# Mono_Audio_Amp.net
KiCad netlist of a schematic drawn in EAGLE
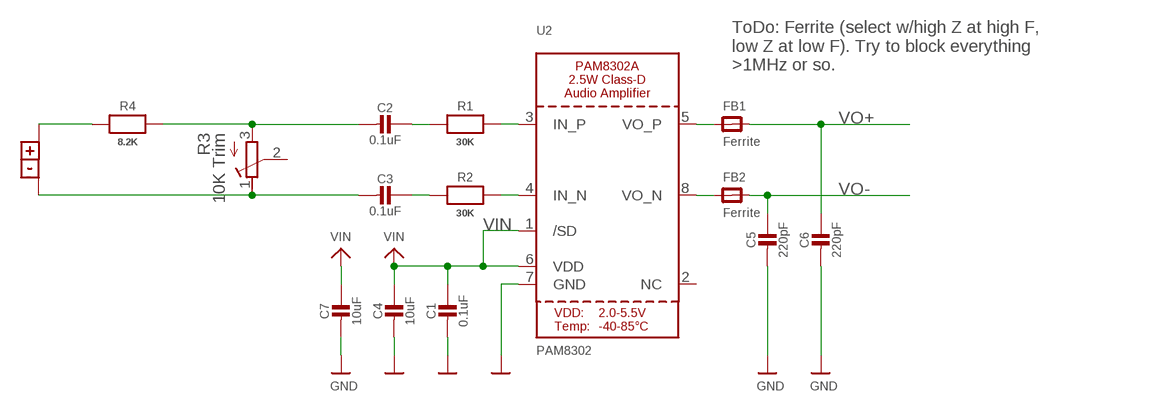
[diagram p0: schematic, sheet 1]

(export (version "E")
  (design (tool "Eeschema 10.0.6"))
  (components
    (comp (ref "C1")
      (value "0.1uF")
      (footprint "eagle-import:0603-NO")
      (libsource (lib "eagle-import") (part "CAP_CERAMIC0603_NO"))
    )
    (comp (ref "C2")
      (value "0.1uF")
      (footprint "eagle-import:0603-NO")
      (libsource (lib "eagle-import") (part "CAP_CERAMIC0603_NO"))
    )
    (comp (ref "C3")
      (value "0.1uF")
      (footprint "eagle-import:0603-NO")
      (libsource (lib "eagle-import") (part "CAP_CERAMIC0603_NO"))
    )
    (comp (ref "C4")
      (value "10uF")
      (footprint "eagle-import:0805-NO")
      (libsource (lib "eagle-import") (part "CAP_CERAMIC0805-NOOUTLINE"))
    )
    (comp (ref "C5")
      (value "220pF")
      (footprint "eagle-import:0603-NO")
      (libsource (lib "eagle-import") (part "CAP_CERAMIC0603_NO"))
    )
    (comp (ref "C6")
      (value "220pF")
      (footprint "eagle-import:0603-NO")
      (libsource (lib "eagle-import") (part "CAP_CERAMIC0603_NO"))
    )
    (comp (ref "C7")
      (value "10uF")
      (footprint "eagle-import:0805-NO")
      (libsource (lib "eagle-import") (part "CAP_CERAMIC0805-NOOUTLINE"))
    )
    (comp (ref "FB1")
      (value "Ferrite")
      (footprint "eagle-import:0603-NO")
      (libsource (lib "eagle-import") (part "FERRITE-0603NO"))
    )
    (comp (ref "FB2")
      (value "Ferrite")
      (footprint "eagle-import:0603-NO")
      (libsource (lib "eagle-import") (part "FERRITE-0603NO"))
    )
    (comp (ref "LS1")
      (value "CMS-18138A-SP")
      (footprint "eagle-import:CUI_CMS-18138A-SP")
      (fields (field (name "MF") "CUI"))
      (libsource (lib "eagle-import") (part "CMS-18138A-SP"))
    )
    (comp (ref "R1")
      (value "30K")
      (footprint "eagle-import:0603-NO")
      (libsource (lib "eagle-import") (part "RESISTOR_0603_NOOUT"))
    )
    (comp (ref "R2")
      (value "30K")
      (footprint "eagle-import:0603-NO")
      (libsource (lib "eagle-import") (part "RESISTOR_0603_NOOUT"))
    )
    (comp (ref "R3")
      (value "10K Trim")
      (footprint "eagle-import:RTRIM3314J")
      (libsource (lib "eagle-import") (part "R-TRIMM3314J"))
    )
    (comp (ref "R4")
      (value "8.2K")
      (footprint "eagle-import:0603-NO")
      (libsource (lib "eagle-import") (part "RESISTOR_0603_NOOUT"))
    )
    (comp (ref "U2")
      (value "PAM8302")
      (footprint "eagle-import:MSOP8_0.65MM")
      (libsource (lib "eagle-import") (part "AUDIOAMP_PAM8302A"))
    )
  )
  (nets
    (net (code "1") (name "/VO+") (class "Default")
      (node (ref "C6") (pin "1") (pinfunction "1_1") (pintype "passive"))
      (node (ref "FB1") (pin "2") (pinfunction "P$2_2") (pintype "passive"))
    )
    (net (code "2") (name "/VO-") (class "Default")
      (node (ref "C5") (pin "1") (pinfunction "1_1") (pintype "passive"))
      (node (ref "FB2") (pin "2") (pinfunction "P$2_2") (pintype "passive"))
    )
    (net (code "3") (name "GND") (class "Default")
      (node (ref "C1") (pin "2") (pinfunction "2_2") (pintype "passive"))
      (node (ref "C4") (pin "2") (pinfunction "2_2") (pintype "passive"))
      (node (ref "C5") (pin "2") (pinfunction "2_2") (pintype "passive"))
      (node (ref "C6") (pin "2") (pinfunction "2_2") (pintype "passive"))
      (node (ref "C7") (pin "2") (pinfunction "2_2") (pintype "passive"))
      (node (ref "U2") (pin "7") (pinfunction "GND_7") (pintype "power_in"))
    )
    (net (code "4") (name "Net-(C2-Pad1)") (class "Default")
      (node (ref "C2") (pin "1") (pinfunction "1_1") (pintype "passive"))
      (node (ref "R1") (pin "1") (pinfunction "1_1") (pintype "passive"))
    )
    (net (code "5") (name "Net-(C3-Pad1)") (class "Default")
      (node (ref "C3") (pin "1") (pinfunction "1_1") (pintype "passive"))
      (node (ref "R2") (pin "1") (pinfunction "1_1") (pintype "passive"))
    )
    (net (code "6") (name "Net-(FB1-P$1)") (class "Default")
      (node (ref "FB1") (pin "1") (pinfunction "P$1_1") (pintype "passive"))
      (node (ref "U2") (pin "5") (pinfunction "VO_P_5") (pintype "output"))
    )
    (net (code "7") (name "Net-(FB2-P$1)") (class "Default")
      (node (ref "FB2") (pin "1") (pinfunction "P$1_1") (pintype "passive"))
      (node (ref "U2") (pin "8") (pinfunction "VO_N_8") (pintype "output"))
    )
    (net (code "8") (name "Net-(LS1-PadP)") (class "Default")
      (node (ref "LS1") (pin "P") (pinfunction "P_P") (pintype "passive"))
      (node (ref "R4") (pin "1") (pinfunction "1_1") (pintype "passive"))
    )
    (net (code "9") (name "Net-(R3-A)") (class "Default")
      (node (ref "C2") (pin "2") (pinfunction "2_2") (pintype "passive"))
      (node (ref "R3") (pin "3") (pinfunction "A_3") (pintype "passive"))
      (node (ref "R4") (pin "2") (pinfunction "2_2") (pintype "passive"))
    )
    (net (code "10") (name "Net-(R3-E)") (class "Default")
      (node (ref "C3") (pin "2") (pinfunction "2_2") (pintype "passive"))
      (node (ref "LS1") (pin "N") (pinfunction "N_N") (pintype "passive"))
      (node (ref "R3") (pin "1") (pinfunction "E_1") (pintype "passive"))
    )
    (net (code "11") (name "Net-(U2-IN_N)") (class "Default")
      (node (ref "R2") (pin "2") (pinfunction "2_2") (pintype "passive"))
      (node (ref "U2") (pin "4") (pinfunction "IN_N_4") (pintype "input"))
    )
    (net (code "12") (name "Net-(U2-IN_P)") (class "Default")
      (node (ref "R1") (pin "2") (pinfunction "2_2") (pintype "passive"))
      (node (ref "U2") (pin "3") (pinfunction "IN_P_3") (pintype "input"))
    )
    (net (code "13") (name "VIN") (class "Default")
      (node (ref "C1") (pin "1") (pinfunction "1_1") (pintype "passive"))
      (node (ref "C4") (pin "1") (pinfunction "1_1") (pintype "passive"))
      (node (ref "C7") (pin "1") (pinfunction "1_1") (pintype "passive"))
      (node (ref "U2") (pin "1") (pinfunction "/SD_1") (pintype "input"))
      (node (ref "U2") (pin "6") (pinfunction "VDD_6") (pintype "power_in"))
    )
    (net (code "14") (name "unconnected-(R3-S-Pad2)") (class "Default")
      (node (ref "R3") (pin "2") (pinfunction "S_2") (pintype "passive"))
    )
    (net (code "15") (name "unconnected-(U2-NC-Pad2)") (class "Default")
      (node (ref "U2") (pin "2") (pinfunction "NC_2") (pintype "no_connect"))
    )
  )
)
